# Makey_Makey_V1_0.net
KiCad netlist of a schematic drawn in Altium Designer
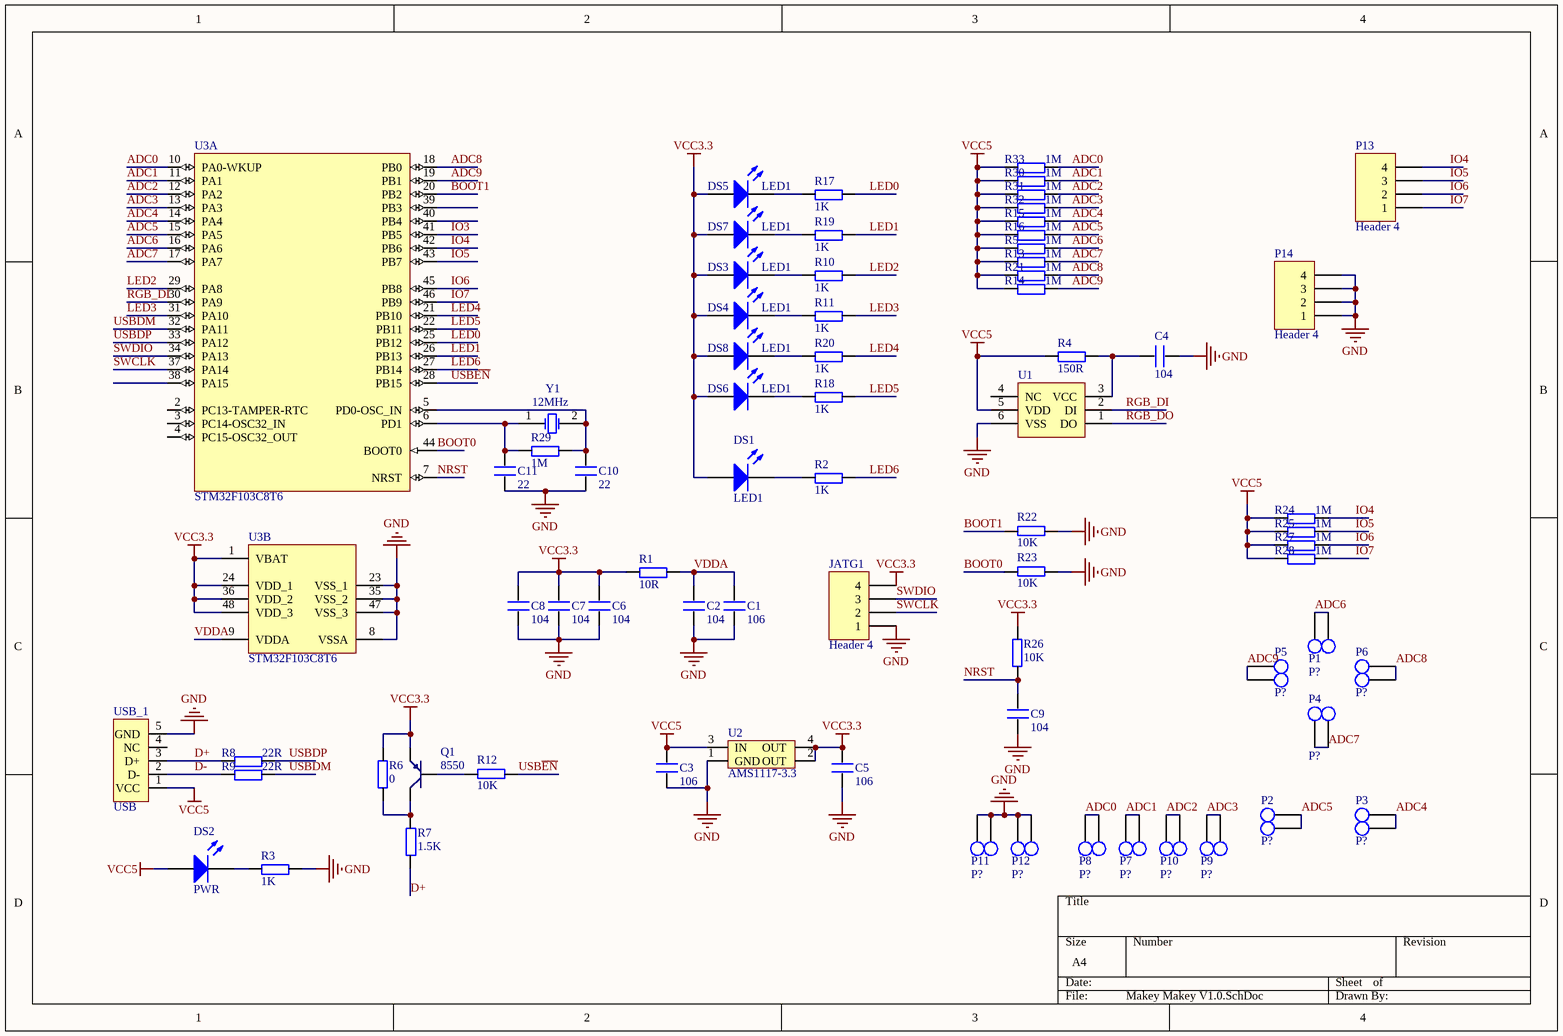
[diagram p0: Makey Makey V1.0.SchDoc]

(export (version "E")
  (design (tool "Eeschema 10.0.6"))
  (components
    (comp (ref "C1") (value "106") (footprint "0603P") (libsource (lib "MiniSTM32 V2.0封装库") (part "C")))
    (comp (ref "C2") (value "104") (footprint "0603P") (libsource (lib "MiniSTM32 V2.0封装库") (part "C")))
    (comp (ref "C3") (value "106") (footprint "0603P") (libsource (lib "MiniSTM32 V2.0封装库") (part "C")))
    (comp (ref "C4") (value "104") (footprint "0603P") (libsource (lib "MiniSTM32 V2.0封装库") (part "C")))
    (comp (ref "C5") (value "106") (footprint "0603P") (libsource (lib "MiniSTM32 V2.0封装库") (part "C")))
    (comp (ref "C6") (value "104") (footprint "0603P") (libsource (lib "MiniSTM32 V2.0封装库") (part "C")))
    (comp (ref "C7") (value "104") (footprint "0603P") (libsource (lib "MiniSTM32 V2.0封装库") (part "C")))
    (comp (ref "C8") (value "104") (footprint "0603P") (libsource (lib "MiniSTM32 V2.0封装库") (part "C")))
    (comp (ref "C9") (value "104") (footprint "0603P") (libsource (lib "MiniSTM32 V2.0封装库") (part "C")))
    (comp (ref "C10") (value "22") (footprint "0603P") (libsource (lib "MiniSTM32 V2.0封装库") (part "C")))
    (comp (ref "C11") (value "22") (footprint "0603P") (libsource (lib "MiniSTM32 V2.0封装库") (part "C")))
    (comp (ref "DS1")
      (value "LED1")
      (footprint "SMDLED")
      (description "Typical RED, GREEN, YELLOW, AMBER GaAs LED")
      (fields (field (name "PUBLISHER") "Altium Limited"))
      (libsource (lib "MiniSTM32 V2.0封装库") (part "LED2"))
    )
    (comp (ref "DS2")
      (value "PWR")
      (footprint "SMDLED")
      (description "Typical RED, GREEN, YELLOW, AMBER GaAs LED")
      (fields (field (name "PUBLISHER") "Altium Limited"))
      (libsource (lib "MiniSTM32 V2.0封装库") (part "LED2"))
    )
    (comp (ref "DS3")
      (value "LED1")
      (footprint "SMDLED")
      (description "Typical RED, GREEN, YELLOW, AMBER GaAs LED")
      (fields (field (name "PUBLISHER") "Altium Limited"))
      (libsource (lib "MiniSTM32 V2.0封装库") (part "LED2"))
    )
    (comp (ref "DS4")
      (value "LED1")
      (footprint "SMDLED")
      (description "Typical RED, GREEN, YELLOW, AMBER GaAs LED")
      (fields (field (name "PUBLISHER") "Altium Limited"))
      (libsource (lib "MiniSTM32 V2.0封装库") (part "LED2"))
    )
    (comp (ref "DS5")
      (value "LED1")
      (footprint "SMDLED")
      (description "Typical RED, GREEN, YELLOW, AMBER GaAs LED")
      (fields (field (name "PUBLISHER") "Altium Limited"))
      (libsource (lib "MiniSTM32 V2.0封装库") (part "LED2"))
    )
    (comp (ref "DS6")
      (value "LED1")
      (footprint "SMDLED")
      (description "Typical RED, GREEN, YELLOW, AMBER GaAs LED")
      (fields (field (name "PUBLISHER") "Altium Limited"))
      (libsource (lib "MiniSTM32 V2.0封装库") (part "LED2"))
    )
    (comp (ref "DS7")
      (value "LED1")
      (footprint "SMDLED")
      (description "Typical RED, GREEN, YELLOW, AMBER GaAs LED")
      (fields (field (name "PUBLISHER") "Altium Limited"))
      (libsource (lib "MiniSTM32 V2.0封装库") (part "LED2"))
    )
    (comp (ref "DS8")
      (value "LED1")
      (footprint "SMDLED")
      (description "Typical RED, GREEN, YELLOW, AMBER GaAs LED")
      (fields (field (name "PUBLISHER") "Altium Limited"))
      (libsource (lib "MiniSTM32 V2.0封装库") (part "LED2"))
    )
    (comp (ref "JATG1")
      (value "Header 4")
      (footprint "HDR1X4")
      (description "Header, 4-Pin")
      (fields (field (name "PUBLISHER") "Altium Limited"))
      (libsource (lib "Miscellaneous Connectors") (part "Header 4"))
    )
    (comp (ref "P1")
      (value "P?")
      (footprint "DIP2")
      (description "DIP2")
      (libsource (lib "MyLib") (part "DIP2"))
    )
    (comp (ref "P2")
      (value "P?")
      (footprint "DIP2R")
      (description "DIP2")
      (libsource (lib "MyLib") (part "DIP2"))
    )
    (comp (ref "P3")
      (value "P?")
      (footprint "DIP2R")
      (description "DIP2")
      (libsource (lib "MyLib") (part "DIP2"))
    )
    (comp (ref "P4")
      (value "P?")
      (footprint "DIP2")
      (description "DIP2")
      (libsource (lib "MyLib") (part "DIP2"))
    )
    (comp (ref "P5")
      (value "P?")
      (footprint "DIP2")
      (description "DIP2")
      (libsource (lib "MyLib") (part "DIP2"))
    )
    (comp (ref "P6")
      (value "P?")
      (footprint "DIP2")
      (description "DIP2")
      (libsource (lib "MyLib") (part "DIP2"))
    )
    (comp (ref "P7")
      (value "P?")
      (footprint "DIP2GND")
      (description "DIP2")
      (libsource (lib "MyLib") (part "DIP2"))
    )
    (comp (ref "P8")
      (value "P?")
      (footprint "DIP2GND")
      (description "DIP2")
      (libsource (lib "MyLib") (part "DIP2"))
    )
    (comp (ref "P9")
      (value "P?")
      (footprint "DIP2GND")
      (description "DIP2")
      (libsource (lib "MyLib") (part "DIP2"))
    )
    (comp (ref "P10")
      (value "P?")
      (footprint "DIP2GND")
      (description "DIP2")
      (libsource (lib "MyLib") (part "DIP2"))
    )
    (comp (ref "P11")
      (value "P?")
      (footprint "DIP2GND")
      (description "DIP2")
      (libsource (lib "MyLib") (part "DIP2"))
    )
    (comp (ref "P12")
      (value "P?")
      (footprint "DIP2GND")
      (description "DIP2")
      (libsource (lib "MyLib") (part "DIP2"))
    )
    (comp (ref "P13")
      (value "Header 4")
      (footprint "HDR1X4")
      (description "Header, 4-Pin")
      (fields (field (name "PUBLISHER") "Altium Limited"))
      (libsource (lib "Miscellaneous Connectors") (part "Header 4"))
    )
    (comp (ref "P14")
      (value "Header 4")
      (footprint "HDR1X4")
      (description "Header, 4-Pin")
      (fields (field (name "PUBLISHER") "Altium Limited"))
      (libsource (lib "Miscellaneous Connectors") (part "Header 4"))
    )
    (comp (ref "Q1")
      (value "8550")
      (footprint "SOT-23R")
      (description "8550/BCW68")
      (libsource (lib "MiniSTM32 V2.0封装库") (part "PNP"))
    )
    (comp (ref "R1") (value "10R") (footprint "0603P") (libsource (lib "MiniSTM32 V2.0封装库") (part "R")))
    (comp (ref "R2") (value "1K") (footprint "0603P") (libsource (lib "MiniSTM32 V2.0封装库") (part "R")))
    (comp (ref "R3") (value "1K") (footprint "0603P") (libsource (lib "MiniSTM32 V2.0封装库") (part "R")))
    (comp (ref "R4") (value "150R") (footprint "0603P") (libsource (lib "MiniSTM32 V2.0封装库") (part "R")))
    (comp (ref "R5") (value "1M") (footprint "0603P") (libsource (lib "MiniSTM32 V2.0封装库") (part "R")))
    (comp (ref "R6") (value "0") (footprint "0603P") (libsource (lib "MiniSTM32 V2.0封装库") (part "R")))
    (comp (ref "R7") (value "1.5K") (footprint "0603P") (libsource (lib "MiniSTM32 V2.0封装库") (part "R")))
    (comp (ref "R8") (value "22R") (footprint "0603P") (libsource (lib "MiniSTM32 V2.0封装库") (part "R")))
    (comp (ref "R9") (value "22R") (footprint "0603P") (libsource (lib "MiniSTM32 V2.0封装库") (part "R")))
    (comp (ref "R10") (value "1K") (footprint "0603P") (libsource (lib "MiniSTM32 V2.0封装库") (part "R")))
    (comp (ref "R11") (value "1K") (footprint "0603P") (libsource (lib "MiniSTM32 V2.0封装库") (part "R")))
    (comp (ref "R12") (value "10K") (footprint "0603P") (libsource (lib "MiniSTM32 V2.0封装库") (part "R")))
    (comp (ref "R13") (value "1M") (footprint "0603P") (libsource (lib "MiniSTM32 V2.0封装库") (part "R")))
    (comp (ref "R14") (value "1M") (footprint "0603P") (libsource (lib "MiniSTM32 V2.0封装库") (part "R")))
    (comp (ref "R15") (value "1M") (footprint "0603P") (libsource (lib "MiniSTM32 V2.0封装库") (part "R")))
    (comp (ref "R16") (value "1M") (footprint "0603P") (libsource (lib "MiniSTM32 V2.0封装库") (part "R")))
    (comp (ref "R17") (value "1K") (footprint "0603P") (libsource (lib "MiniSTM32 V2.0封装库") (part "R")))
    (comp (ref "R18") (value "1K") (footprint "0603P") (libsource (lib "MiniSTM32 V2.0封装库") (part "R")))
    (comp (ref "R19") (value "1K") (footprint "0603P") (libsource (lib "MiniSTM32 V2.0封装库") (part "R")))
    (comp (ref "R20") (value "1K") (footprint "0603P") (libsource (lib "MiniSTM32 V2.0封装库") (part "R")))
    (comp (ref "R21") (value "1M") (footprint "0603P") (libsource (lib "MiniSTM32 V2.0封装库") (part "R")))
    (comp (ref "R22") (value "10K") (footprint "0603P") (libsource (lib "MiniSTM32 V2.0封装库") (part "R")))
    (comp (ref "R23") (value "10K") (footprint "0603P") (libsource (lib "MiniSTM32 V2.0封装库") (part "R")))
    (comp (ref "R24") (value "1M") (footprint "0603P") (libsource (lib "MiniSTM32 V2.0封装库") (part "R")))
    (comp (ref "R25") (value "1M") (footprint "0603P") (libsource (lib "MiniSTM32 V2.0封装库") (part "R")))
    (comp (ref "R26") (value "10K") (footprint "0603P") (libsource (lib "MiniSTM32 V2.0封装库") (part "R")))
    (comp (ref "R27") (value "1M") (footprint "0603P") (libsource (lib "MiniSTM32 V2.0封装库") (part "R")))
    (comp (ref "R28") (value "1M") (footprint "0603P") (libsource (lib "MiniSTM32 V2.0封装库") (part "R")))
    (comp (ref "R29") (value "1M") (footprint "0603P") (libsource (lib "MiniSTM32 V2.0封装库") (part "R")))
    (comp (ref "R30") (value "1M") (footprint "0603P") (libsource (lib "MiniSTM32 V2.0封装库") (part "R")))
    (comp (ref "R31") (value "1M") (footprint "0603P") (libsource (lib "MiniSTM32 V2.0封装库") (part "R")))
    (comp (ref "R32") (value "1M") (footprint "0603P") (libsource (lib "MiniSTM32 V2.0封装库") (part "R")))
    (comp (ref "R33") (value "1M") (footprint "0603P") (libsource (lib "MiniSTM32 V2.0封装库") (part "R")))
    (comp (ref "U1")
      (value "?")
      (footprint "WS2812-5050RBG")
      (description "WS2812-5050RGB")
      (libsource (lib "MyLib") (part "WS2812-5050RGB"))
    )
    (comp (ref "U2")
      (value "AMS1117-3.3")
      (footprint "AMS1117")
      (libsource (lib "MiniSTM32 V2.0封装库") (part "AMS1117"))
    )
    (comp (ref "U3")
      (value "STM32F103C8T6")
      (footprint "LQFP48_N")
      (libsource (lib "STMicroelectronics STM32 F1") (part "STM32F103C8T6"))
    )
    (comp (ref "USB_1")
      (value "USB")
      (footprint "USB/SM0.8-6H5")
      (libsource (lib "MiniSTM32 V2.0封装库") (part "USB5"))
    )
    (comp (ref "Y1")
      (value "12MHz")
      (footprint "XTAL_US")
      (description "Crystal Oscillator")
      (fields (field (name "PUBLISHER") "Altium Limited"))
      (libsource (lib "MiniSTM32 V2.0封装库") (part "XTAL"))
    )
  )
  (nets
    (net (code "1") (name "/ADC0") (class "Default")
      (node (ref "P8") (pin "1") (pinfunction "1_1") (pintype "passive"))
      (node (ref "P8") (pin "2") (pinfunction "2_2") (pintype "passive"))
      (node (ref "R33") (pin "2") (pintype "passive"))
      (node (ref "U3") (pin "10") (pinfunction "PA0-WKUP_10") (pintype "bidirectional"))
    )
    (net (code "2") (name "/ADC1") (class "Default")
      (node (ref "P7") (pin "1") (pinfunction "1_1") (pintype "passive"))
      (node (ref "P7") (pin "2") (pinfunction "2_2") (pintype "passive"))
      (node (ref "R30") (pin "2") (pintype "passive"))
      (node (ref "U3") (pin "11") (pinfunction "PA1_11") (pintype "bidirectional"))
    )
    (net (code "3") (name "/ADC2") (class "Default")
      (node (ref "P10") (pin "1") (pinfunction "1_1") (pintype "passive"))
      (node (ref "P10") (pin "2") (pinfunction "2_2") (pintype "passive"))
      (node (ref "R31") (pin "2") (pintype "passive"))
      (node (ref "U3") (pin "12") (pinfunction "PA2_12") (pintype "bidirectional"))
    )
    (net (code "4") (name "/ADC3") (class "Default")
      (node (ref "P9") (pin "1") (pinfunction "1_1") (pintype "passive"))
      (node (ref "P9") (pin "2") (pinfunction "2_2") (pintype "passive"))
      (node (ref "R32") (pin "2") (pintype "passive"))
      (node (ref "U3") (pin "13") (pinfunction "PA3_13") (pintype "bidirectional"))
    )
    (net (code "5") (name "/ADC4") (class "Default")
      (node (ref "P3") (pin "1") (pinfunction "1_1") (pintype "passive"))
      (node (ref "P3") (pin "2") (pinfunction "2_2") (pintype "passive"))
      (node (ref "R15") (pin "2") (pintype "passive"))
      (node (ref "U3") (pin "14") (pinfunction "PA4_14") (pintype "bidirectional"))
    )
    (net (code "6") (name "/ADC5") (class "Default")
      (node (ref "P2") (pin "1") (pinfunction "1_1") (pintype "passive"))
      (node (ref "P2") (pin "2") (pinfunction "2_2") (pintype "passive"))
      (node (ref "R16") (pin "2") (pintype "passive"))
      (node (ref "U3") (pin "15") (pinfunction "PA5_15") (pintype "bidirectional"))
    )
    (net (code "7") (name "/ADC6") (class "Default")
      (node (ref "P1") (pin "1") (pinfunction "1_1") (pintype "passive"))
      (node (ref "P1") (pin "2") (pinfunction "2_2") (pintype "passive"))
      (node (ref "R5") (pin "2") (pintype "passive"))
      (node (ref "U3") (pin "16") (pinfunction "PA6_16") (pintype "bidirectional"))
    )
    (net (code "8") (name "/ADC7") (class "Default")
      (node (ref "P4") (pin "1") (pinfunction "1_1") (pintype "passive"))
      (node (ref "P4") (pin "2") (pinfunction "2_2") (pintype "passive"))
      (node (ref "R13") (pin "2") (pintype "passive"))
      (node (ref "U3") (pin "17") (pinfunction "PA7_17") (pintype "bidirectional"))
    )
    (net (code "9") (name "/ADC8") (class "Default")
      (node (ref "P6") (pin "1") (pinfunction "1_1") (pintype "passive"))
      (node (ref "P6") (pin "2") (pinfunction "2_2") (pintype "passive"))
      (node (ref "R21") (pin "2") (pintype "passive"))
      (node (ref "U3") (pin "18") (pinfunction "PB0_18") (pintype "bidirectional"))
    )
    (net (code "10") (name "/ADC9") (class "Default")
      (node (ref "P5") (pin "1") (pinfunction "1_1") (pintype "passive"))
      (node (ref "P5") (pin "2") (pinfunction "2_2") (pintype "passive"))
      (node (ref "R14") (pin "2") (pintype "passive"))
      (node (ref "U3") (pin "19") (pinfunction "PB1_19") (pintype "bidirectional"))
    )
    (net (code "11") (name "/BOOT0") (class "Default")
      (node (ref "R23") (pin "2") (pintype "passive"))
      (node (ref "U3") (pin "44") (pinfunction "BOOT0_44") (pintype "input"))
    )
    (net (code "12") (name "/BOOT1") (class "Default")
      (node (ref "R22") (pin "2") (pintype "passive"))
      (node (ref "U3") (pin "20") (pinfunction "PB2_20") (pintype "bidirectional"))
    )
    (net (code "13") (name "/D+") (class "Default")
      (node (ref "R7") (pin "1") (pintype "passive"))
      (node (ref "R8") (pin "1") (pintype "passive"))
      (node (ref "USB_1") (pin "3") (pinfunction "D+_3") (pintype "passive"))
    )
    (net (code "14") (name "/D-") (class "Default")
      (node (ref "R9") (pin "1") (pintype "passive"))
      (node (ref "USB_1") (pin "2") (pinfunction "D-_2") (pintype "passive"))
    )
    (net (code "15") (name "/IO3") (class "Default")
      (node (ref "U3") (pin "41") (pinfunction "PB5_41") (pintype "bidirectional"))
    )
    (net (code "16") (name "/IO4") (class "Default")
      (node (ref "P13") (pin "4") (pinfunction "4_4") (pintype "passive"))
      (node (ref "R24") (pin "2") (pintype "passive"))
      (node (ref "U3") (pin "42") (pinfunction "PB6_42") (pintype "bidirectional"))
    )
    (net (code "17") (name "/IO5") (class "Default")
      (node (ref "P13") (pin "3") (pinfunction "3_3") (pintype "passive"))
      (node (ref "R25") (pin "2") (pintype "passive"))
      (node (ref "U3") (pin "43") (pinfunction "PB7_43") (pintype "bidirectional"))
    )
    (net (code "18") (name "/IO6") (class "Default")
      (node (ref "P13") (pin "2") (pinfunction "2_2") (pintype "passive"))
      (node (ref "R27") (pin "2") (pintype "passive"))
      (node (ref "U3") (pin "45") (pinfunction "PB8_45") (pintype "bidirectional"))
    )
    (net (code "19") (name "/IO7") (class "Default")
      (node (ref "P13") (pin "1") (pinfunction "1_1") (pintype "passive"))
      (node (ref "R28") (pin "2") (pintype "passive"))
      (node (ref "U3") (pin "46") (pinfunction "PB9_46") (pintype "bidirectional"))
    )
    (net (code "20") (name "/LED0") (class "Default")
      (node (ref "R17") (pin "2") (pintype "passive"))
      (node (ref "U3") (pin "25") (pinfunction "PB12_25") (pintype "bidirectional"))
    )
    (net (code "21") (name "/LED1") (class "Default")
      (node (ref "R19") (pin "2") (pintype "passive"))
      (node (ref "U3") (pin "26") (pinfunction "PB13_26") (pintype "bidirectional"))
    )
    (net (code "22") (name "/LED2") (class "Default")
      (node (ref "R10") (pin "2") (pintype "passive"))
      (node (ref "U3") (pin "29") (pinfunction "PA8_29") (pintype "bidirectional"))
    )
    (net (code "23") (name "/LED3") (class "Default")
      (node (ref "R11") (pin "2") (pintype "passive"))
      (node (ref "U3") (pin "31") (pinfunction "PA10_31") (pintype "bidirectional"))
    )
    (net (code "24") (name "/LED4") (class "Default")
      (node (ref "R20") (pin "2") (pintype "passive"))
      (node (ref "U3") (pin "21") (pinfunction "PB10_21") (pintype "bidirectional"))
    )
    (net (code "25") (name "/LED5") (class "Default")
      (node (ref "R18") (pin "2") (pintype "passive"))
      (node (ref "U3") (pin "22") (pinfunction "PB11_22") (pintype "bidirectional"))
    )
    (net (code "26") (name "/LED6") (class "Default")
      (node (ref "R2") (pin "2") (pintype "passive"))
      (node (ref "U3") (pin "27") (pinfunction "PB14_27") (pintype "bidirectional"))
    )
    (net (code "27") (name "/NRST") (class "Default")
      (node (ref "C9") (pin "2") (pintype "passive"))
      (node (ref "R26") (pin "2") (pintype "passive"))
      (node (ref "U3") (pin "7") (pinfunction "NRST_7") (pintype "bidirectional"))
    )
    (net (code "28") (name "/RGB_DI") (class "Default")
      (node (ref "U1") (pin "2") (pinfunction "DI_2") (pintype "passive"))
      (node (ref "U3") (pin "30") (pinfunction "PA9_30") (pintype "bidirectional"))
    )
    (net (code "29") (name "/RGB_DO") (class "Default")
      (node (ref "U1") (pin "1") (pinfunction "DO_1") (pintype "passive"))
    )
    (net (code "30") (name "/SWCLK") (class "Default")
      (node (ref "JATG1") (pin "2") (pinfunction "2_2") (pintype "passive"))
      (node (ref "U3") (pin "37") (pinfunction "PA14_37") (pintype "bidirectional"))
    )
    (net (code "31") (name "/SWDIO") (class "Default")
      (node (ref "JATG1") (pin "3") (pinfunction "3_3") (pintype "passive"))
      (node (ref "U3") (pin "34") (pinfunction "PA13_34") (pintype "bidirectional"))
    )
    (net (code "32") (name "/USBDM") (class "Default")
      (node (ref "R9") (pin "2") (pintype "passive"))
      (node (ref "U3") (pin "32") (pinfunction "PA11_32") (pintype "bidirectional"))
    )
    (net (code "33") (name "/USBDP") (class "Default")
      (node (ref "R8") (pin "2") (pintype "passive"))
      (node (ref "U3") (pin "33") (pinfunction "PA12_33") (pintype "bidirectional"))
    )
    (net (code "34") (name "/USB~{EN}") (class "Default")
      (node (ref "R12") (pin "1") (pintype "passive"))
      (node (ref "U3") (pin "28") (pinfunction "PB15_28") (pintype "bidirectional"))
    )
    (net (code "35") (name "/VDDA") (class "Default")
      (node (ref "C1") (pin "2") (pintype "passive"))
      (node (ref "C2") (pin "2") (pintype "passive"))
      (node (ref "R1") (pin "2") (pintype "passive"))
      (node (ref "U3") (pin "9") (pinfunction "VDDA_9") (pintype "power_in"))
    )
    (net (code "36") (name "GND") (class "Default")
      (node (ref "C1") (pin "1") (pintype "passive"))
      (node (ref "C10") (pin "2") (pintype "passive"))
      (node (ref "C11") (pin "2") (pintype "passive"))
      (node (ref "C2") (pin "1") (pintype "passive"))
      (node (ref "C3") (pin "1") (pintype "passive"))
      (node (ref "C4") (pin "2") (pintype "passive"))
      (node (ref "C5") (pin "1") (pintype "passive"))
      (node (ref "C6") (pin "1") (pintype "passive"))
      (node (ref "C7") (pin "1") (pintype "passive"))
      (node (ref "C8") (pin "1") (pintype "passive"))
      (node (ref "C9") (pin "1") (pintype "passive"))
      (node (ref "JATG1") (pin "1") (pinfunction "1_1") (pintype "passive"))
      (node (ref "P11") (pin "1") (pinfunction "1_1") (pintype "passive"))
      (node (ref "P11") (pin "2") (pinfunction "2_2") (pintype "passive"))
      (node (ref "P12") (pin "1") (pinfunction "1_1") (pintype "passive"))
      (node (ref "P12") (pin "2") (pinfunction "2_2") (pintype "passive"))
      (node (ref "P14") (pin "1") (pinfunction "1_1") (pintype "passive"))
      (node (ref "P14") (pin "2") (pinfunction "2_2") (pintype "passive"))
      (node (ref "P14") (pin "3") (pinfunction "3_3") (pintype "passive"))
      (node (ref "P14") (pin "4") (pinfunction "4_4") (pintype "passive"))
      (node (ref "R22") (pin "1") (pintype "passive"))
      (node (ref "R23") (pin "1") (pintype "passive"))
      (node (ref "R3") (pin "2") (pintype "passive"))
      (node (ref "U1") (pin "6") (pinfunction "VSS_6") (pintype "passive"))
      (node (ref "U2") (pin "1") (pinfunction "GND_1") (pintype "passive"))
      (node (ref "U3") (pin "23") (pinfunction "VSS_1_23") (pintype "power_in"))
      (node (ref "U3") (pin "35") (pinfunction "VSS_2_35") (pintype "power_in"))
      (node (ref "U3") (pin "47") (pinfunction "VSS_3_47") (pintype "power_in"))
      (node (ref "U3") (pin "8") (pinfunction "VSSA_8") (pintype "power_in"))
      (node (ref "USB_1") (pin "5") (pinfunction "GND_5") (pintype "passive"))
    )
    (net (code "37") (name "Net-(DS1-K)") (class "Default")
      (node (ref "DS1") (pin "2") (pinfunction "K_2") (pintype "passive"))
      (node (ref "R2") (pin "1") (pintype "passive"))
    )
    (net (code "38") (name "Net-(DS2-K)") (class "Default")
      (node (ref "DS2") (pin "2") (pinfunction "K_2") (pintype "passive"))
      (node (ref "R3") (pin "1") (pintype "passive"))
    )
    (net (code "39") (name "Net-(DS3-K)") (class "Default")
      (node (ref "DS3") (pin "2") (pinfunction "K_2") (pintype "passive"))
      (node (ref "R10") (pin "1") (pintype "passive"))
    )
    (net (code "40") (name "Net-(DS4-K)") (class "Default")
      (node (ref "DS4") (pin "2") (pinfunction "K_2") (pintype "passive"))
      (node (ref "R11") (pin "1") (pintype "passive"))
    )
    (net (code "41") (name "Net-(DS5-K)") (class "Default")
      (node (ref "DS5") (pin "2") (pinfunction "K_2") (pintype "passive"))
      (node (ref "R17") (pin "1") (pintype "passive"))
    )
    (net (code "42") (name "Net-(DS6-K)") (class "Default")
      (node (ref "DS6") (pin "2") (pinfunction "K_2") (pintype "passive"))
      (node (ref "R18") (pin "1") (pintype "passive"))
    )
    (net (code "43") (name "Net-(DS7-K)") (class "Default")
      (node (ref "DS7") (pin "2") (pinfunction "K_2") (pintype "passive"))
      (node (ref "R19") (pin "1") (pintype "passive"))
    )
    (net (code "44") (name "Net-(DS8-K)") (class "Default")
      (node (ref "DS8") (pin "2") (pinfunction "K_2") (pintype "passive"))
      (node (ref "R20") (pin "1") (pintype "passive"))
    )
    (net (code "45") (name "Net-(Q1-B)") (class "Default")
      (node (ref "Q1") (pin "2") (pinfunction "B_2") (pintype "passive"))
      (node (ref "R12") (pin "2") (pintype "passive"))
    )
    (net (code "46") (name "Net-(Q1-C)") (class "Default")
      (node (ref "Q1") (pin "3") (pinfunction "C_3") (pintype "passive"))
      (node (ref "R6") (pin "2") (pintype "passive"))
      (node (ref "R7") (pin "2") (pintype "passive"))
    )
    (net (code "47") (name "Net-(U1-VCC)") (class "Default")
      (node (ref "C4") (pin "1") (pintype "passive"))
      (node (ref "R4") (pin "2") (pintype "passive"))
      (node (ref "U1") (pin "3") (pinfunction "VCC_3") (pintype "passive"))
    )
    (net (code "48") (name "Net-(U3A-PD0-OSC_IN)") (class "Default")
      (node (ref "C10") (pin "1") (pintype "passive"))
      (node (ref "R29") (pin "2") (pintype "passive"))
      (node (ref "U3") (pin "5") (pinfunction "PD0-OSC_IN_5") (pintype "bidirectional"))
      (node (ref "Y1") (pin "2") (pinfunction "OSC2_2") (pintype "passive"))
    )
    (net (code "49") (name "Net-(U3A-PD1)") (class "Default")
      (node (ref "C11") (pin "1") (pintype "passive"))
      (node (ref "R29") (pin "1") (pintype "passive"))
      (node (ref "U3") (pin "6") (pinfunction "PD1_6") (pintype "bidirectional"))
      (node (ref "Y1") (pin "1") (pinfunction "OSC1_1") (pintype "passive"))
    )
    (net (code "50") (name "VCC3.3") (class "Default")
      (node (ref "C5") (pin "2") (pintype "passive"))
      (node (ref "C6") (pin "2") (pintype "passive"))
      (node (ref "C7") (pin "2") (pintype "passive"))
      (node (ref "C8") (pin "2") (pintype "passive"))
      (node (ref "DS1") (pin "1") (pinfunction "A_1") (pintype "passive"))
      (node (ref "DS3") (pin "1") (pinfunction "A_1") (pintype "passive"))
      (node (ref "DS4") (pin "1") (pinfunction "A_1") (pintype "passive"))
      (node (ref "DS5") (pin "1") (pinfunction "A_1") (pintype "passive"))
      (node (ref "DS6") (pin "1") (pinfunction "A_1") (pintype "passive"))
      (node (ref "DS7") (pin "1") (pinfunction "A_1") (pintype "passive"))
      (node (ref "DS8") (pin "1") (pinfunction "A_1") (pintype "passive"))
      (node (ref "JATG1") (pin "4") (pinfunction "4_4") (pintype "passive"))
      (node (ref "Q1") (pin "1") (pinfunction "E_1") (pintype "passive"))
      (node (ref "R1") (pin "1") (pintype "passive"))
      (node (ref "R26") (pin "1") (pintype "passive"))
      (node (ref "R6") (pin "1") (pintype "passive"))
      (node (ref "U2") (pin "2") (pinfunction "OUT_2") (pintype "passive"))
      (node (ref "U2") (pin "4") (pinfunction "OUT_4") (pintype "passive"))
      (node (ref "U3") (pin "1") (pinfunction "VBAT_1") (pintype "power_in"))
      (node (ref "U3") (pin "24") (pinfunction "VDD_1_24") (pintype "power_in"))
      (node (ref "U3") (pin "36") (pinfunction "VDD_2_36") (pintype "power_in"))
      (node (ref "U3") (pin "48") (pinfunction "VDD_3_48") (pintype "power_in"))
    )
    (net (code "51") (name "VCC5") (class "Default")
      (node (ref "C3") (pin "2") (pintype "passive"))
      (node (ref "DS2") (pin "1") (pinfunction "A_1") (pintype "passive"))
      (node (ref "R13") (pin "1") (pintype "passive"))
      (node (ref "R14") (pin "1") (pintype "passive"))
      (node (ref "R15") (pin "1") (pintype "passive"))
      (node (ref "R16") (pin "1") (pintype "passive"))
      (node (ref "R21") (pin "1") (pintype "passive"))
      (node (ref "R24") (pin "1") (pintype "passive"))
      (node (ref "R25") (pin "1") (pintype "passive"))
      (node (ref "R27") (pin "1") (pintype "passive"))
      (node (ref "R28") (pin "1") (pintype "passive"))
      (node (ref "R30") (pin "1") (pintype "passive"))
      (node (ref "R31") (pin "1") (pintype "passive"))
      (node (ref "R32") (pin "1") (pintype "passive"))
      (node (ref "R33") (pin "1") (pintype "passive"))
      (node (ref "R4") (pin "1") (pintype "passive"))
      (node (ref "R5") (pin "1") (pintype "passive"))
      (node (ref "U1") (pin "5") (pinfunction "VDD_5") (pintype "passive"))
      (node (ref "U2") (pin "3") (pinfunction "IN_3") (pintype "passive"))
      (node (ref "USB_1") (pin "1") (pinfunction "VCC_1") (pintype "passive"))
    )
    (net (code "52") (name "unconnected-(U1-NC-Pad4)") (class "Default")
      (node (ref "U1") (pin "4") (pinfunction "NC_4") (pintype "passive"))
    )
    (net (code "53") (name "unconnected-(U3A-PA15-Pad38)") (class "Default")
      (node (ref "U3") (pin "38") (pinfunction "PA15_38") (pintype "bidirectional"))
    )
    (net (code "54") (name "unconnected-(U3A-PB3-Pad39)") (class "Default")
      (node (ref "U3") (pin "39") (pinfunction "PB3_39") (pintype "bidirectional"))
    )
    (net (code "55") (name "unconnected-(U3A-PB4-Pad40)") (class "Default")
      (node (ref "U3") (pin "40") (pinfunction "PB4_40") (pintype "bidirectional"))
    )
    (net (code "56") (name "unconnected-(U3A-PC13-TAMPER-RTC-Pad2)") (class "Default")
      (node (ref "U3") (pin "2") (pinfunction "PC13-TAMPER-RTC_2") (pintype "bidirectional"))
    )
    (net (code "57") (name "unconnected-(U3A-PC14-OSC32_IN-Pad3)") (class "Default")
      (node (ref "U3") (pin "3") (pinfunction "PC14-OSC32_IN_3") (pintype "bidirectional"))
    )
    (net (code "58") (name "unconnected-(U3A-PC15-OSC32_OUT-Pad4)") (class "Default")
      (node (ref "U3") (pin "4") (pinfunction "PC15-OSC32_OUT_4") (pintype "bidirectional"))
    )
    (net (code "59") (name "unconnected-(USB_1-NC-Pad4)") (class "Default")
      (node (ref "USB_1") (pin "4") (pinfunction "NC_4") (pintype "passive"))
    )
  )
)
